# VRB.net
KiCad netlist of a schematic drawn in Altium Designer
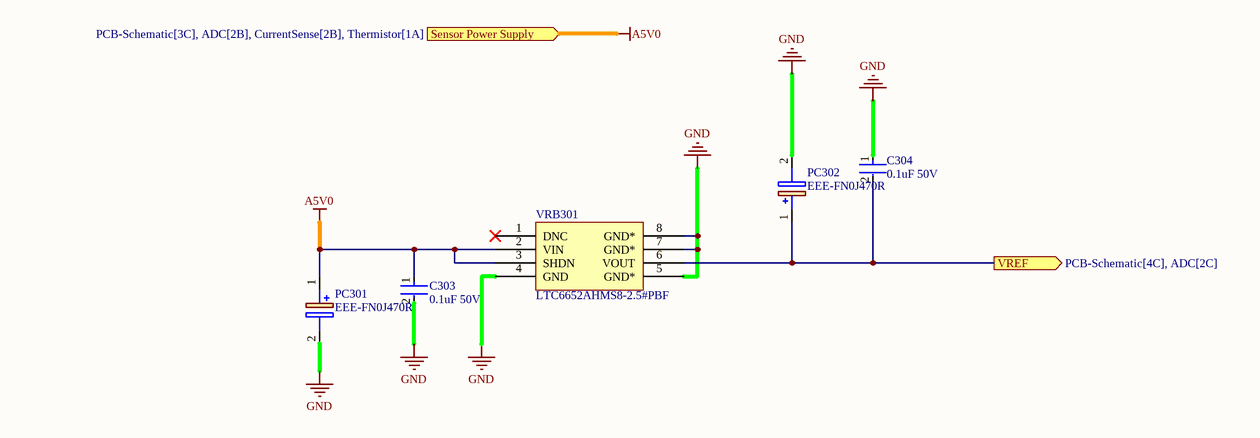
[diagram p0: VRB.SchDoc]

(export (version "E")
  (design (tool "Eeschema 10.0.6"))
  (components
    (comp (ref "C303")
      (value "0.1uF 50V")
      (footprint "FP-CC0603-DA-MFG")
      (description "CAP CER 0.1UF 50V X7R 0603")
      (fields
        (field (name "MANUFACTURER") "YAGEO")
        (field (name "OCTOPART") "https://octopart.com/cc0603kpx7r9bb104-yageo-12885113")
      )
      (libsource (lib "Altium Content Vault") (part "11868f565c42a9108669ba33697ecf6"))
    )
    (comp (ref "C304")
      (value "0.1uF 50V")
      (footprint "FP-CC0603-DA-MFG")
      (description "CAP CER 0.1UF 50V X7R 0603")
      (fields
        (field (name "MANUFACTURER") "YAGEO")
        (field (name "OCTOPART") "https://octopart.com/cc0603kpx7r9bb104-yageo-12885113")
      )
      (libsource (lib "Altium Content Vault") (part "11868f565c42a9108669ba33697ecf6"))
    )
    (comp (ref "PC301")
      (value "EEE-FN0J470R")
      (footprint "ECEN403Sensors:EEE1AA220WR")
      (description "Capacitor Polarised")
      (fields (field (name "MOUSER PART NUMBER") "667-EEE-FN0J470R"))
      (libsource (lib "ECEN403Sensors") (part "EEE-FN0J470R"))
    )
    (comp (ref "PC302")
      (value "EEE-FN0J470R")
      (footprint "ECEN403Sensors:EEE1AA220WR")
      (description "Capacitor Polarised")
      (fields (field (name "MOUSER PART NUMBER") "667-EEE-FN0J470R"))
      (libsource (lib "") (part "EEE-FN0J470R_1"))
    )
    (comp (ref "VRB301")
      (value "LTC6652AHMS8-2.5#PBF")
      (footprint "LTC6652AHMS8-2.5#PBF")
      (libsource (lib "ECEN403Sensors") (part "LTC6652AHMS8-2.5#PBF"))
    )
  )
  (nets
    (net (code "1") (name "/VREF") (class "Default")
      (node (ref "C304") (pin "2") (pinfunction "2_2") (pintype "passive"))
      (node (ref "PC302") (pin "1") (pinfunction "+_1") (pintype "passive"))
      (node (ref "VRB301") (pin "6") (pinfunction "VOUT_6") (pintype "passive"))
    )
    (net (code "2") (name "A5V0") (class "Default")
      (node (ref "C303") (pin "1") (pinfunction "1_1") (pintype "passive"))
      (node (ref "PC301") (pin "1") (pinfunction "+_1") (pintype "passive"))
      (node (ref "VRB301") (pin "2") (pinfunction "VIN_2") (pintype "passive"))
      (node (ref "VRB301") (pin "3") (pinfunction "SHDN_3") (pintype "passive"))
    )
    (net (code "3") (name "GND") (class "Default")
      (node (ref "C303") (pin "2") (pinfunction "2_2") (pintype "passive"))
      (node (ref "C304") (pin "1") (pinfunction "1_1") (pintype "passive"))
      (node (ref "PC301") (pin "2") (pinfunction "-_2") (pintype "passive"))
      (node (ref "PC302") (pin "2") (pinfunction "-_2") (pintype "passive"))
      (node (ref "VRB301") (pin "4") (pinfunction "GND_4") (pintype "passive"))
      (node (ref "VRB301") (pin "5") (pinfunction "GND*_5") (pintype "passive"))
      (node (ref "VRB301") (pin "7") (pinfunction "GND*_7") (pintype "passive"))
      (node (ref "VRB301") (pin "8") (pinfunction "GND*_8") (pintype "passive"))
    )
    (net (code "4") (name "unconnected-(VRB301-DNC-Pad1)") (class "Default")
      (node (ref "VRB301") (pin "1") (pinfunction "DNC_1") (pintype "passive+no_connect"))
    )
  )
)
